# SCH_TCC-ESP32_2025-09-30.net
KiCad netlist of a schematic drawn in EasyEDA
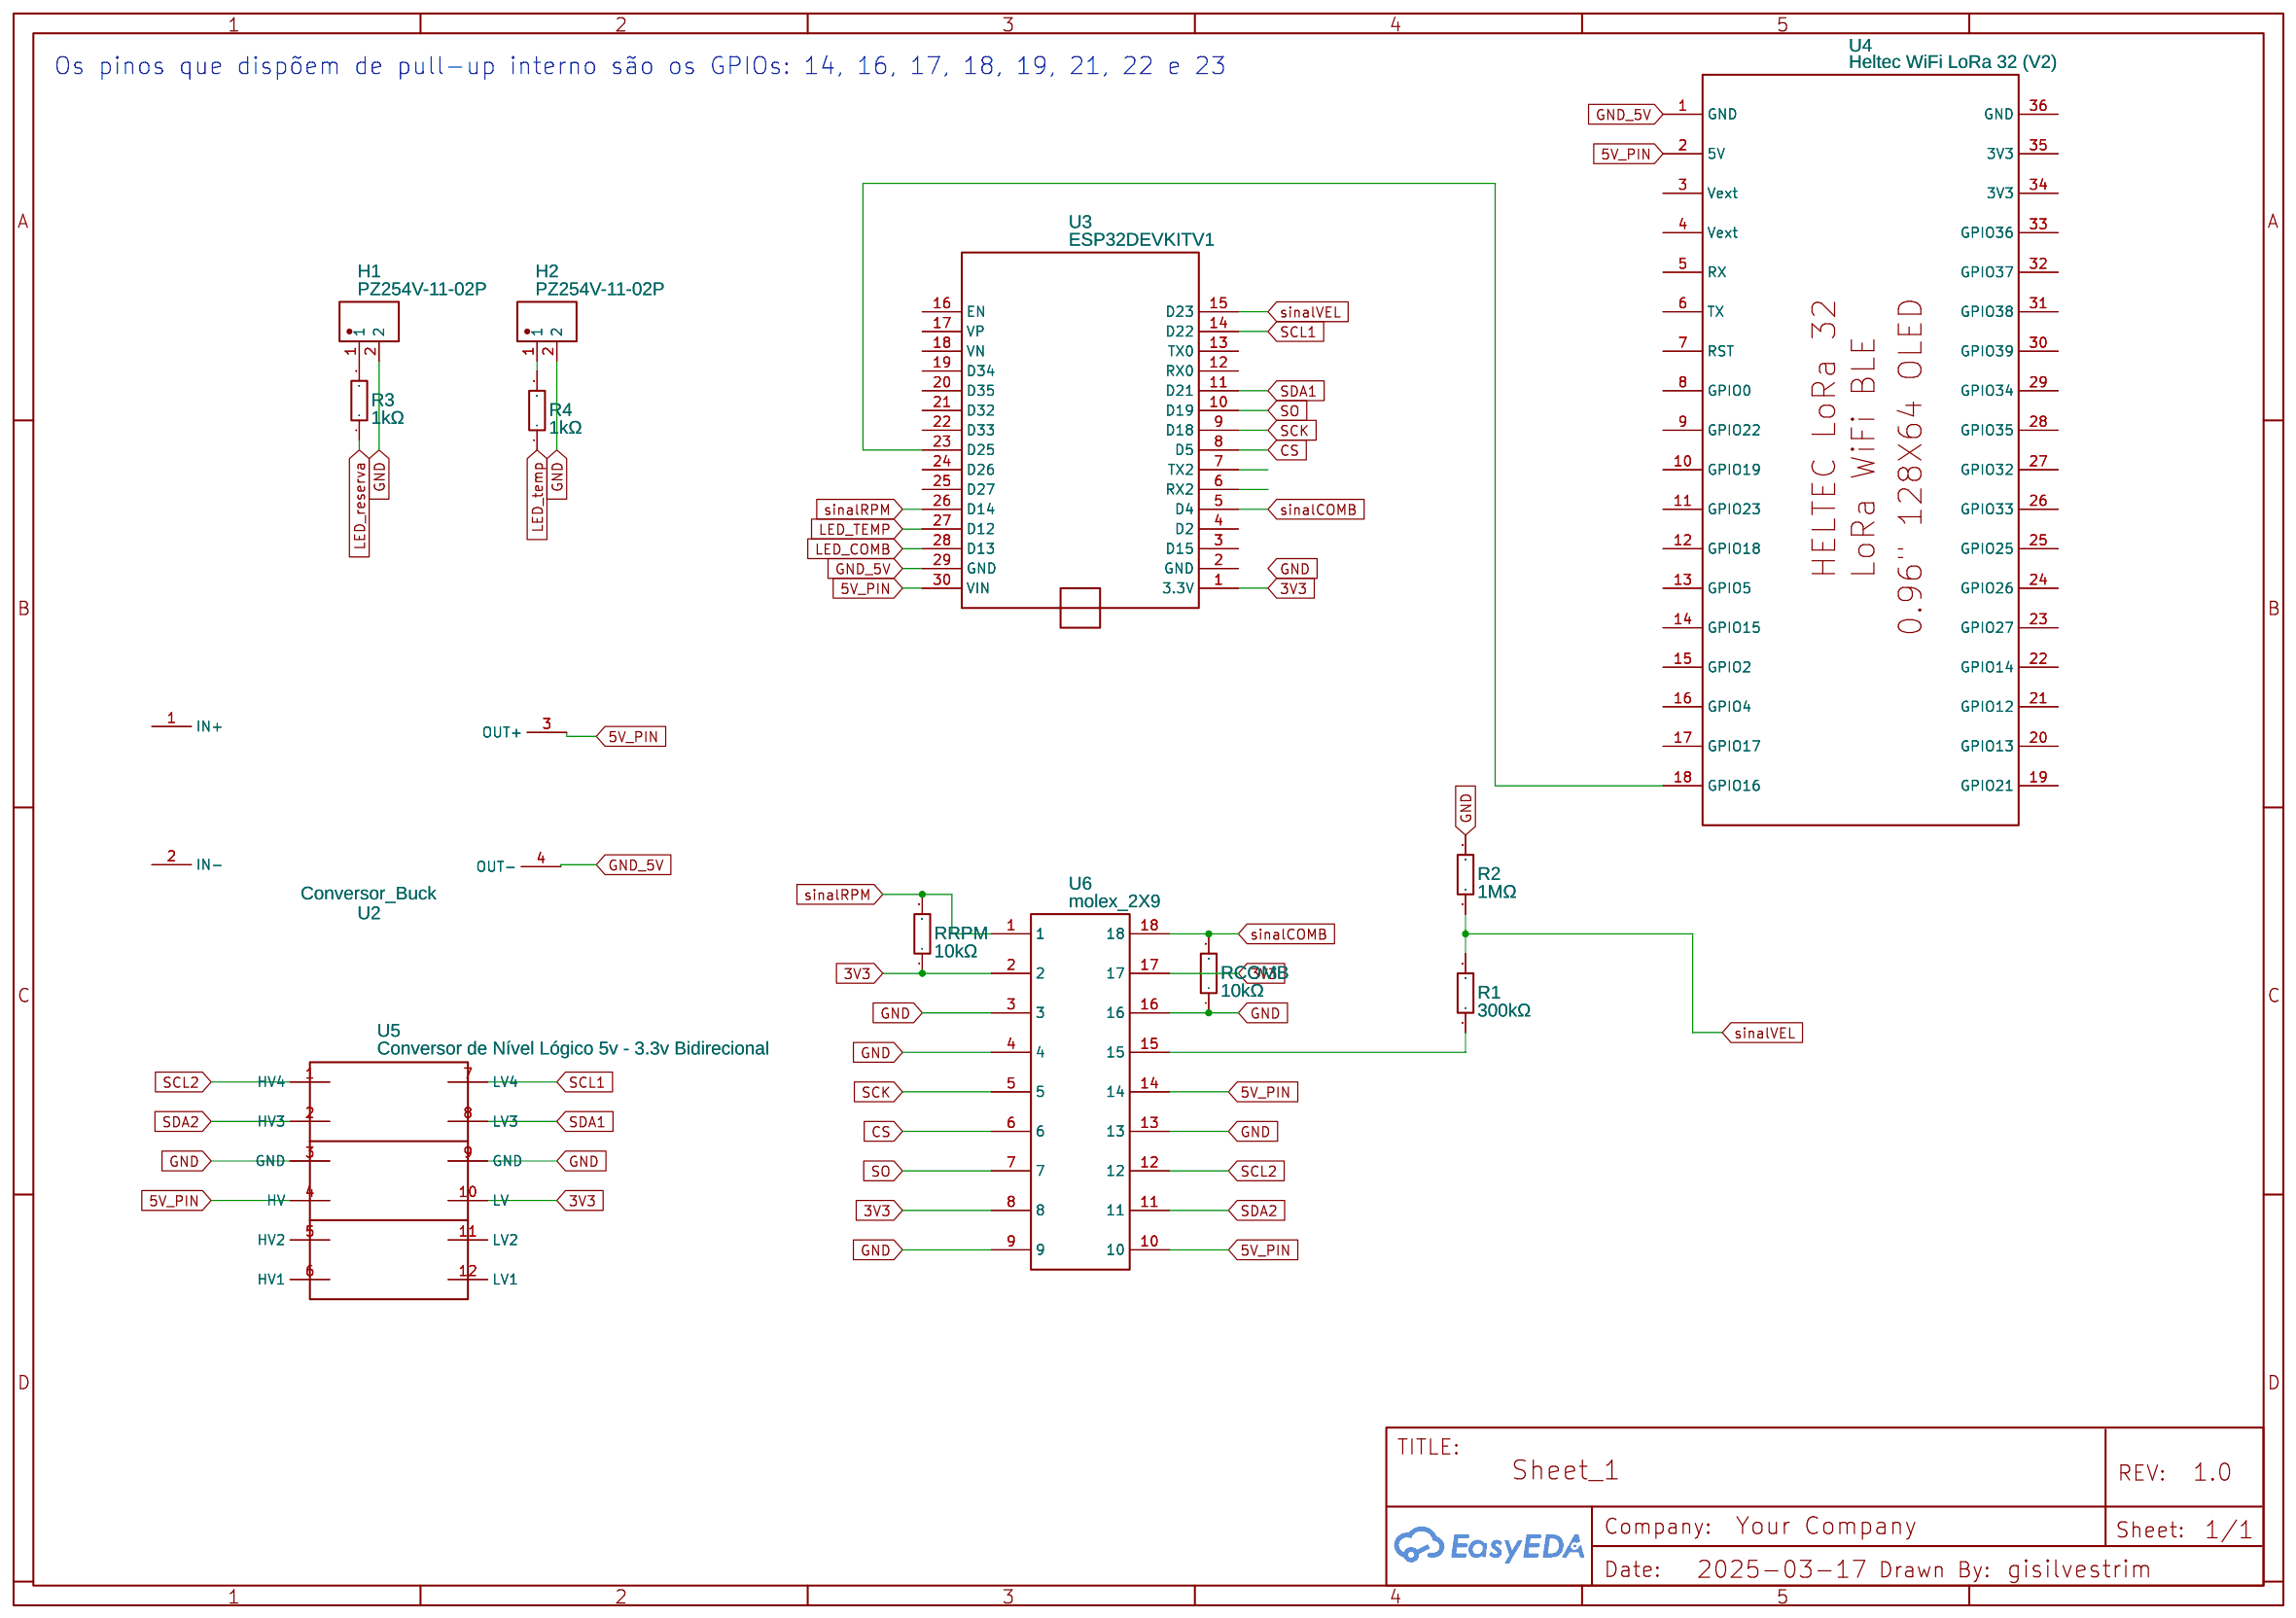
[diagram p0: schematic sheet]

(export (version "E")
  (design (tool "Eeschema 10.0.6"))
  (components
    (comp (ref "H1")
      (value "PZ254V-11-02P")
      (fields (field (name "Manufacturer") "XFCN(兴飞)"))
      (libsource (lib "") (part "PZ254V-11-02P"))
    )
    (comp (ref "H2")
      (value "PZ254V-11-02P")
      (fields (field (name "Manufacturer") "XFCN(兴飞)"))
      (libsource (lib "") (part "PZ254V-11-02P"))
    )
    (comp (ref "R1")
      (value "300kΩ")
      (fields (field (name "Manufacturer Part") "RC0402FR-07300KL") (field (name "Manufacturer") "YAGEO(国巨)"))
      (libsource (lib "") (part "RC0402FR-07300KL"))
    )
    (comp (ref "R2")
      (value "1MΩ")
      (fields (field (name "Manufacturer Part") "RC0402FR-071ML") (field (name "Manufacturer") "YAGEO(国巨)"))
      (libsource (lib "") (part "RC0402FR-071ML"))
    )
    (comp (ref "R3")
      (value "1kΩ")
      (fields (field (name "Manufacturer Part") "RC0603FR-071KL") (field (name "Manufacturer") "YAGEO(国巨)"))
      (libsource (lib "") (part "RC0603FR-071KL"))
    )
    (comp (ref "R4")
      (value "1kΩ")
      (fields (field (name "Manufacturer Part") "RC0603FR-071KL") (field (name "Manufacturer") "YAGEO(国巨)"))
      (libsource (lib "") (part "RC0603FR-071KL"))
    )
    (comp (ref "RCOMB")
      (value "10kΩ")
      (fields (field (name "Manufacturer Part") "RC0402FR-0710KL") (field (name "Manufacturer") "YAGEO(国巨)"))
      (libsource (lib "") (part "RC0402FR-0710KL"))
    )
    (comp (ref "RRPM")
      (value "10kΩ")
      (fields (field (name "Manufacturer Part") "RC0402FR-0710KL") (field (name "Manufacturer") "YAGEO(国巨)"))
      (libsource (lib "") (part "RC0402FR-0710KL_1"))
    )
    (comp (ref "U2") (value "Conversor_Buck") (libsource (lib "") (part "Conversor_Buck")))
    (comp (ref "U3") (value "ESP32DEVKITV1") (libsource (lib "") (part "ESP32DEVKITV1")))
    (comp (ref "U4")
      (value "Heltec WiFi LoRa 32 (V2)")
      (fields
        (field (name "Manufacturer Part") "Heltec WiFi LoRa 32(V2)")
        (field (name "Manufacturer") "Heltec")
      )
      (libsource (lib "") (part "Heltec WiFi LoRa 32 (V2)"))
    )
    (comp (ref "U5")
      (value "Conversor de Nível Lógico 5v - 3.3v Bidirecional")
      (libsource (lib "") (part "Conversor de Nível Lógico 5v - 3.3v Bidirecional"))
    )
    (comp (ref "U6") (value "molex_2X9") (libsource (lib "") (part "molex_2X9")))
  )
  (nets
    (net (code "1") (name "3V3") (class "Default")
      (node (ref "RRPM") (pin "1") (pinfunction "1_1") (pintype "input"))
      (node (ref "U3") (pin "1") (pinfunction "3.3V_1") (pintype "unspecified"))
      (node (ref "U5") (pin "10") (pinfunction "LV_10") (pintype "unspecified"))
      (node (ref "U6") (pin "17") (pinfunction "17_17") (pintype "unspecified"))
      (node (ref "U6") (pin "2") (pinfunction "2_2") (pintype "unspecified"))
      (node (ref "U6") (pin "8") (pinfunction "8_8") (pintype "unspecified"))
    )
    (net (code "2") (name "5V_PIN") (class "Default")
      (node (ref "U2") (pin "3") (pinfunction "OUT+_3") (pintype "unspecified"))
      (node (ref "U3") (pin "30") (pinfunction "VIN_30") (pintype "unspecified"))
      (node (ref "U4") (pin "2") (pinfunction "5V_2") (pintype "unspecified"))
      (node (ref "U5") (pin "4") (pinfunction "HV_4") (pintype "unspecified"))
      (node (ref "U6") (pin "10") (pinfunction "10_10") (pintype "unspecified"))
      (node (ref "U6") (pin "14") (pinfunction "14_14") (pintype "unspecified"))
    )
    (net (code "3") (name "CS") (class "Default")
      (node (ref "U3") (pin "8") (pinfunction "D5_8") (pintype "unspecified"))
      (node (ref "U6") (pin "6") (pinfunction "6_6") (pintype "unspecified"))
    )
    (net (code "4") (name "GND") (class "Default")
      (node (ref "H1") (pin "2") (pinfunction "2_2") (pintype "unspecified"))
      (node (ref "H2") (pin "2") (pinfunction "2_2") (pintype "unspecified"))
      (node (ref "R2") (pin "2") (pinfunction "2_2") (pintype "input"))
      (node (ref "RCOMB") (pin "1") (pinfunction "1_1") (pintype "input"))
      (node (ref "U5") (pin "3") (pinfunction "GND_3") (pintype "unspecified"))
      (node (ref "U5") (pin "9") (pinfunction "GND_9") (pintype "unspecified"))
      (node (ref "U6") (pin "13") (pinfunction "13_13") (pintype "unspecified"))
      (node (ref "U6") (pin "16") (pinfunction "16_16") (pintype "unspecified"))
      (node (ref "U6") (pin "3") (pinfunction "3_3") (pintype "unspecified"))
      (node (ref "U6") (pin "4") (pinfunction "4_4") (pintype "unspecified"))
      (node (ref "U6") (pin "9") (pinfunction "9_9") (pintype "unspecified"))
    )
    (net (code "5") (name "GND_5V") (class "Default")
      (node (ref "U2") (pin "4") (pinfunction "OUT-_4") (pintype "unspecified"))
      (node (ref "U3") (pin "29") (pinfunction "GND_29") (pintype "unspecified"))
      (node (ref "U4") (pin "1") (pinfunction "GND_1") (pintype "unspecified"))
    )
    (net (code "6") (name "LED_COMB") (class "Default")
      (node (ref "U3") (pin "28") (pinfunction "D13_28") (pintype "unspecified"))
    )
    (net (code "7") (name "LED_TEMP") (class "Default")
      (node (ref "U3") (pin "27") (pinfunction "D12_27") (pintype "unspecified"))
    )
    (net (code "8") (name "LED_reserva") (class "Default")
      (node (ref "R3") (pin "1") (pinfunction "1_1") (pintype "input"))
    )
    (net (code "9") (name "LED_temp") (class "Default")
      (node (ref "R4") (pin "1") (pinfunction "1_1") (pintype "input"))
    )
    (net (code "10") (name "Net-(H1-Pad1)") (class "Default")
      (node (ref "H1") (pin "1") (pinfunction "1_1") (pintype "unspecified"))
      (node (ref "R3") (pin "2") (pinfunction "2_2") (pintype "input"))
    )
    (net (code "11") (name "Net-(H2-Pad1)") (class "Default")
      (node (ref "H2") (pin "1") (pinfunction "1_1") (pintype "unspecified"))
      (node (ref "R4") (pin "2") (pinfunction "2_2") (pintype "input"))
    )
    (net (code "12") (name "Net-(R1-Pad1)") (class "Default")
      (node (ref "R1") (pin "1") (pinfunction "1_1") (pintype "input"))
      (node (ref "U6") (pin "15") (pinfunction "15_15") (pintype "unspecified"))
    )
    (net (code "13") (name "Net-(U3-D25)") (class "Default")
      (node (ref "U3") (pin "23") (pinfunction "D25_23") (pintype "unspecified"))
      (node (ref "U4") (pin "18") (pinfunction "GPIO16_18") (pintype "unspecified"))
    )
    (net (code "14") (name "SCK") (class "Default")
      (node (ref "U3") (pin "9") (pinfunction "D18_9") (pintype "unspecified"))
      (node (ref "U6") (pin "5") (pinfunction "5_5") (pintype "unspecified"))
    )
    (net (code "15") (name "SCL1") (class "Default")
      (node (ref "U3") (pin "14") (pinfunction "D22_14") (pintype "unspecified"))
      (node (ref "U5") (pin "7") (pinfunction "LV4_7") (pintype "unspecified"))
    )
    (net (code "16") (name "SCL2") (class "Default")
      (node (ref "U5") (pin "1") (pinfunction "HV4_1") (pintype "unspecified"))
      (node (ref "U6") (pin "12") (pinfunction "12_12") (pintype "unspecified"))
    )
    (net (code "17") (name "SDA1") (class "Default")
      (node (ref "U3") (pin "11") (pinfunction "D21_11") (pintype "unspecified"))
      (node (ref "U5") (pin "8") (pinfunction "LV3_8") (pintype "unspecified"))
    )
    (net (code "18") (name "SDA2") (class "Default")
      (node (ref "U5") (pin "2") (pinfunction "HV3_2") (pintype "unspecified"))
      (node (ref "U6") (pin "11") (pinfunction "11_11") (pintype "unspecified"))
    )
    (net (code "19") (name "SO") (class "Default")
      (node (ref "U3") (pin "10") (pinfunction "D19_10") (pintype "unspecified"))
      (node (ref "U6") (pin "7") (pinfunction "7_7") (pintype "unspecified"))
    )
    (net (code "20") (name "sinalCOMB") (class "Default")
      (node (ref "RCOMB") (pin "2") (pinfunction "2_2") (pintype "input"))
      (node (ref "U3") (pin "5") (pinfunction "D4_5") (pintype "unspecified"))
      (node (ref "U6") (pin "18") (pinfunction "18_18") (pintype "unspecified"))
    )
    (net (code "21") (name "sinalRPM") (class "Default")
      (node (ref "RRPM") (pin "2") (pinfunction "2_2") (pintype "input"))
      (node (ref "U3") (pin "26") (pinfunction "D14_26") (pintype "unspecified"))
      (node (ref "U6") (pin "1") (pinfunction "1_1") (pintype "unspecified"))
    )
    (net (code "22") (name "sinalVEL") (class "Default")
      (node (ref "R1") (pin "2") (pinfunction "2_2") (pintype "input"))
      (node (ref "R2") (pin "1") (pinfunction "1_1") (pintype "input"))
      (node (ref "U3") (pin "15") (pinfunction "D23_15") (pintype "unspecified"))
    )
    (net (code "23") (name "unconnected-(U2-IN+-Pad1)") (class "Default")
      (node (ref "U2") (pin "1") (pinfunction "IN+_1") (pintype "unspecified"))
    )
    (net (code "24") (name "unconnected-(U2-IN--Pad2)") (class "Default")
      (node (ref "U2") (pin "2") (pinfunction "IN-_2") (pintype "unspecified"))
    )
    (net (code "25") (name "unconnected-(U3-D2-Pad4)") (class "Default")
      (node (ref "U3") (pin "4") (pinfunction "D2_4") (pintype "unspecified"))
    )
    (net (code "26") (name "unconnected-(U3-D15-Pad3)") (class "Default")
      (node (ref "U3") (pin "3") (pinfunction "D15_3") (pintype "unspecified"))
    )
    (net (code "27") (name "unconnected-(U3-D26-Pad24)") (class "Default")
      (node (ref "U3") (pin "24") (pinfunction "D26_24") (pintype "unspecified"))
    )
    (net (code "28") (name "unconnected-(U3-D27-Pad25)") (class "Default")
      (node (ref "U3") (pin "25") (pinfunction "D27_25") (pintype "unspecified"))
    )
    (net (code "29") (name "unconnected-(U3-D32-Pad21)") (class "Default")
      (node (ref "U3") (pin "21") (pinfunction "D32_21") (pintype "unspecified"))
    )
    (net (code "30") (name "unconnected-(U3-D33-Pad22)") (class "Default")
      (node (ref "U3") (pin "22") (pinfunction "D33_22") (pintype "unspecified"))
    )
    (net (code "31") (name "unconnected-(U3-D34-Pad19)") (class "Default")
      (node (ref "U3") (pin "19") (pinfunction "D34_19") (pintype "unspecified"))
    )
    (net (code "32") (name "unconnected-(U3-D35-Pad20)") (class "Default")
      (node (ref "U3") (pin "20") (pinfunction "D35_20") (pintype "unspecified"))
    )
    (net (code "33") (name "unconnected-(U3-EN-Pad16)") (class "Default")
      (node (ref "U3") (pin "16") (pinfunction "EN_16") (pintype "unspecified"))
    )
    (net (code "34") (name "unconnected-(U3-GND-Pad2)") (class "Default")
      (node (ref "U3") (pin "2") (pinfunction "GND_2") (pintype "unspecified"))
    )
    (net (code "35") (name "unconnected-(U3-RX0-Pad12)") (class "Default")
      (node (ref "U3") (pin "12") (pinfunction "RX0_12") (pintype "unspecified"))
    )
    (net (code "36") (name "unconnected-(U3-RX2-Pad6)") (class "Default")
      (node (ref "U3") (pin "6") (pinfunction "RX2_6") (pintype "unspecified"))
    )
    (net (code "37") (name "unconnected-(U3-TX0-Pad13)") (class "Default")
      (node (ref "U3") (pin "13") (pinfunction "TX0_13") (pintype "unspecified"))
    )
    (net (code "38") (name "unconnected-(U3-TX2-Pad7)") (class "Default")
      (node (ref "U3") (pin "7") (pinfunction "TX2_7") (pintype "unspecified"))
    )
    (net (code "39") (name "unconnected-(U3-VN-Pad18)") (class "Default")
      (node (ref "U3") (pin "18") (pinfunction "VN_18") (pintype "unspecified"))
    )
    (net (code "40") (name "unconnected-(U3-VP-Pad17)") (class "Default")
      (node (ref "U3") (pin "17") (pinfunction "VP_17") (pintype "unspecified"))
    )
    (net (code "41") (name "unconnected-(U4-3V3-Pad34)") (class "Default")
      (node (ref "U4") (pin "34") (pinfunction "3V3_34") (pintype "unspecified"))
    )
    (net (code "42") (name "unconnected-(U4-3V3-Pad35)") (class "Default")
      (node (ref "U4") (pin "35") (pinfunction "3V3_35") (pintype "unspecified"))
    )
    (net (code "43") (name "unconnected-(U4-GND-Pad36)") (class "Default")
      (node (ref "U4") (pin "36") (pinfunction "GND_36") (pintype "unspecified"))
    )
    (net (code "44") (name "unconnected-(U4-GPIO0-Pad8)") (class "Default")
      (node (ref "U4") (pin "8") (pinfunction "GPIO0_8") (pintype "unspecified"))
    )
    (net (code "45") (name "unconnected-(U4-GPIO2-Pad15)") (class "Default")
      (node (ref "U4") (pin "15") (pinfunction "GPIO2_15") (pintype "unspecified"))
    )
    (net (code "46") (name "unconnected-(U4-GPIO4-Pad16)") (class "Default")
      (node (ref "U4") (pin "16") (pinfunction "GPIO4_16") (pintype "unspecified"))
    )
    (net (code "47") (name "unconnected-(U4-GPIO5-Pad13)") (class "Default")
      (node (ref "U4") (pin "13") (pinfunction "GPIO5_13") (pintype "unspecified"))
    )
    (net (code "48") (name "unconnected-(U4-GPIO12-Pad21)") (class "Default")
      (node (ref "U4") (pin "21") (pinfunction "GPIO12_21") (pintype "unspecified"))
    )
    (net (code "49") (name "unconnected-(U4-GPIO13-Pad20)") (class "Default")
      (node (ref "U4") (pin "20") (pinfunction "GPIO13_20") (pintype "unspecified"))
    )
    (net (code "50") (name "unconnected-(U4-GPIO14-Pad22)") (class "Default")
      (node (ref "U4") (pin "22") (pinfunction "GPIO14_22") (pintype "unspecified"))
    )
    (net (code "51") (name "unconnected-(U4-GPIO15-Pad14)") (class "Default")
      (node (ref "U4") (pin "14") (pinfunction "GPIO15_14") (pintype "unspecified"))
    )
    (net (code "52") (name "unconnected-(U4-GPIO17-Pad17)") (class "Default")
      (node (ref "U4") (pin "17") (pinfunction "GPIO17_17") (pintype "unspecified"))
    )
    (net (code "53") (name "unconnected-(U4-GPIO18-Pad12)") (class "Default")
      (node (ref "U4") (pin "12") (pinfunction "GPIO18_12") (pintype "unspecified"))
    )
    (net (code "54") (name "unconnected-(U4-GPIO19-Pad10)") (class "Default")
      (node (ref "U4") (pin "10") (pinfunction "GPIO19_10") (pintype "unspecified"))
    )
    (net (code "55") (name "unconnected-(U4-GPIO21-Pad19)") (class "Default")
      (node (ref "U4") (pin "19") (pinfunction "GPIO21_19") (pintype "unspecified"))
    )
    (net (code "56") (name "unconnected-(U4-GPIO22-Pad9)") (class "Default")
      (node (ref "U4") (pin "9") (pinfunction "GPIO22_9") (pintype "unspecified"))
    )
    (net (code "57") (name "unconnected-(U4-GPIO23-Pad11)") (class "Default")
      (node (ref "U4") (pin "11") (pinfunction "GPIO23_11") (pintype "unspecified"))
    )
    (net (code "58") (name "unconnected-(U4-GPIO25-Pad25)") (class "Default")
      (node (ref "U4") (pin "25") (pinfunction "GPIO25_25") (pintype "unspecified"))
    )
    (net (code "59") (name "unconnected-(U4-GPIO26-Pad24)") (class "Default")
      (node (ref "U4") (pin "24") (pinfunction "GPIO26_24") (pintype "unspecified"))
    )
    (net (code "60") (name "unconnected-(U4-GPIO27-Pad23)") (class "Default")
      (node (ref "U4") (pin "23") (pinfunction "GPIO27_23") (pintype "unspecified"))
    )
    (net (code "61") (name "unconnected-(U4-GPIO32-Pad27)") (class "Default")
      (node (ref "U4") (pin "27") (pinfunction "GPIO32_27") (pintype "unspecified"))
    )
    (net (code "62") (name "unconnected-(U4-GPIO33-Pad26)") (class "Default")
      (node (ref "U4") (pin "26") (pinfunction "GPIO33_26") (pintype "unspecified"))
    )
    (net (code "63") (name "unconnected-(U4-GPIO34-Pad29)") (class "Default")
      (node (ref "U4") (pin "29") (pinfunction "GPIO34_29") (pintype "unspecified"))
    )
    (net (code "64") (name "unconnected-(U4-GPIO35-Pad28)") (class "Default")
      (node (ref "U4") (pin "28") (pinfunction "GPIO35_28") (pintype "unspecified"))
    )
    (net (code "65") (name "unconnected-(U4-GPIO36-Pad33)") (class "Default")
      (node (ref "U4") (pin "33") (pinfunction "GPIO36_33") (pintype "unspecified"))
    )
    (net (code "66") (name "unconnected-(U4-GPIO37-Pad32)") (class "Default")
      (node (ref "U4") (pin "32") (pinfunction "GPIO37_32") (pintype "unspecified"))
    )
    (net (code "67") (name "unconnected-(U4-GPIO38-Pad31)") (class "Default")
      (node (ref "U4") (pin "31") (pinfunction "GPIO38_31") (pintype "unspecified"))
    )
    (net (code "68") (name "unconnected-(U4-GPIO39-Pad30)") (class "Default")
      (node (ref "U4") (pin "30") (pinfunction "GPIO39_30") (pintype "unspecified"))
    )
    (net (code "69") (name "unconnected-(U4-RST-Pad7)") (class "Default")
      (node (ref "U4") (pin "7") (pinfunction "RST_7") (pintype "unspecified"))
    )
    (net (code "70") (name "unconnected-(U4-RX-Pad5)") (class "Default")
      (node (ref "U4") (pin "5") (pinfunction "RX_5") (pintype "unspecified"))
    )
    (net (code "71") (name "unconnected-(U4-TX-Pad6)") (class "Default")
      (node (ref "U4") (pin "6") (pinfunction "TX_6") (pintype "unspecified"))
    )
    (net (code "72") (name "unconnected-(U4-Vext-Pad3)") (class "Default")
      (node (ref "U4") (pin "3") (pinfunction "Vext_3") (pintype "unspecified"))
    )
    (net (code "73") (name "unconnected-(U4-Vext-Pad4)") (class "Default")
      (node (ref "U4") (pin "4") (pinfunction "Vext_4") (pintype "unspecified"))
    )
    (net (code "74") (name "unconnected-(U5-HV1-Pad6)") (class "Default")
      (node (ref "U5") (pin "6") (pinfunction "HV1_6") (pintype "unspecified"))
    )
    (net (code "75") (name "unconnected-(U5-HV2-Pad5)") (class "Default")
      (node (ref "U5") (pin "5") (pinfunction "HV2_5") (pintype "unspecified"))
    )
    (net (code "76") (name "unconnected-(U5-LV1-Pad12)") (class "Default")
      (node (ref "U5") (pin "12") (pinfunction "LV1_12") (pintype "unspecified"))
    )
    (net (code "77") (name "unconnected-(U5-LV2-Pad11)") (class "Default")
      (node (ref "U5") (pin "11") (pinfunction "LV2_11") (pintype "unspecified"))
    )
  )
)
